# LED.net
KiCad netlist of a schematic drawn in Altium Designer
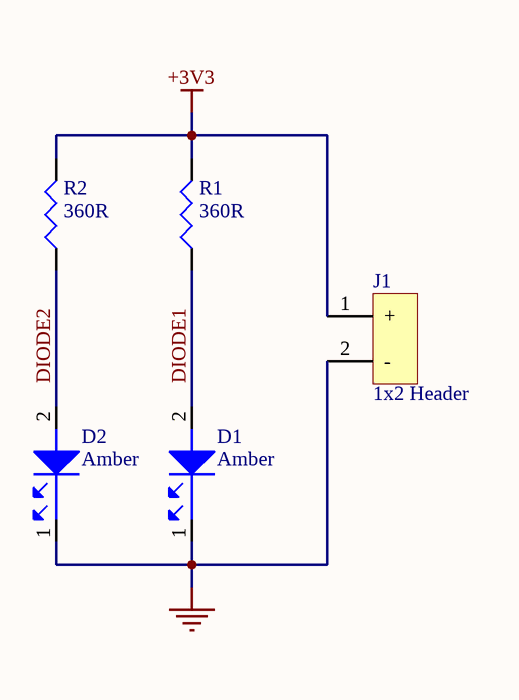
[diagram p0: LED.SchDoc]

(export (version "E")
  (design (tool "Eeschema 10.0.6"))
  (components
    (comp (ref "D1")
      (value "Amber")
      (footprint "LED 0603 AMBER")
      (description "PANASONIC - LNJ437W84RA - LED, AMBER, 0.8MM X 1.1MM, 25MCD, 590NM")
      (fields
        (field (name "MANUFACTURER") "Panasonic SSG")
        (field (name "MANUFACTURER PART NUMBER") "LNJ437W84RA")
      )
      (libsource (lib "LED_SchLib") (part "LNJ437W84RA"))
    )
    (comp (ref "D2")
      (value "Amber")
      (footprint "LED 0603 AMBER")
      (description "PANASONIC - LNJ437W84RA - LED, AMBER, 0.8MM X 1.1MM, 25MCD, 590NM")
      (fields
        (field (name "MANUFACTURER") "Panasonic SSG")
        (field (name "MANUFACTURER PART NUMBER") "LNJ437W84RA")
      )
      (libsource (lib "LED_SchLib") (part "LNJ437W84RA"))
    )
    (comp (ref "J1")
      (value "1x2 Header")
      (footprint "Header 1x2")
      (description "Conn Wire to Board HDR 2 POS 2.54mm Solder ST Thru-Hole Bag")
      (fields (field (name "MANUFACTURER") "Molex") (field (name "MANUFACTURER PART NUMBER") "22-29-2021"))
      (libsource (lib "LED_SchLib") (part "22-29-2021"))
    )
    (comp (ref "R1")
      (value "360R")
      (footprint "R0805")
      (description "Res Thick Film 0805 360 Ohm 1% 0.125W(1/8W) ±100ppm/C Molded SMD Automotive Paper T/R")
      (fields
        (field (name "MANUFACTURER") "Vishay")
        (field (name "MANUFACTURER PART NUMBER") "CRCW0805360RFKEA")
      )
      (libsource (lib "LED_SchLib") (part "CRCW0805360RFKEA"))
    )
    (comp (ref "R2")
      (value "360R")
      (footprint "R0805")
      (description "Res Thick Film 0805 360 Ohm 1% 0.125W(1/8W) ±100ppm/C Molded SMD Automotive Paper T/R")
      (fields
        (field (name "MANUFACTURER") "Vishay")
        (field (name "MANUFACTURER PART NUMBER") "CRCW0805360RFKEA")
      )
      (libsource (lib "LED_SchLib") (part "CRCW0805360RFKEA"))
    )
  )
  (nets
    (net (code "1") (name "+3V3") (class "Default")
      (node (ref "J1") (pin "1") (pinfunction "+_1") (pintype "passive"))
      (node (ref "R1") (pin "2") (pinfunction "2_2") (pintype "passive"))
      (node (ref "R2") (pin "2") (pinfunction "2_2") (pintype "passive"))
    )
    (net (code "2") (name "/DIODE1") (class "Default")
      (node (ref "D1") (pin "2") (pinfunction "2_2") (pintype "passive"))
      (node (ref "R1") (pin "1") (pinfunction "1_1") (pintype "passive"))
    )
    (net (code "3") (name "/DIODE2") (class "Default")
      (node (ref "D2") (pin "2") (pinfunction "2_2") (pintype "passive"))
      (node (ref "R2") (pin "1") (pinfunction "1_1") (pintype "passive"))
    )
    (net (code "4") (name "GND") (class "Default")
      (node (ref "D1") (pin "1") (pinfunction "1_1") (pintype "passive"))
      (node (ref "D2") (pin "1") (pinfunction "1_1") (pintype "passive"))
      (node (ref "J1") (pin "2") (pinfunction "-_2") (pintype "passive"))
    )
  )
)
